# cc3200-shield-v2_0.net
KiCad netlist of a schematic drawn in EAGLE
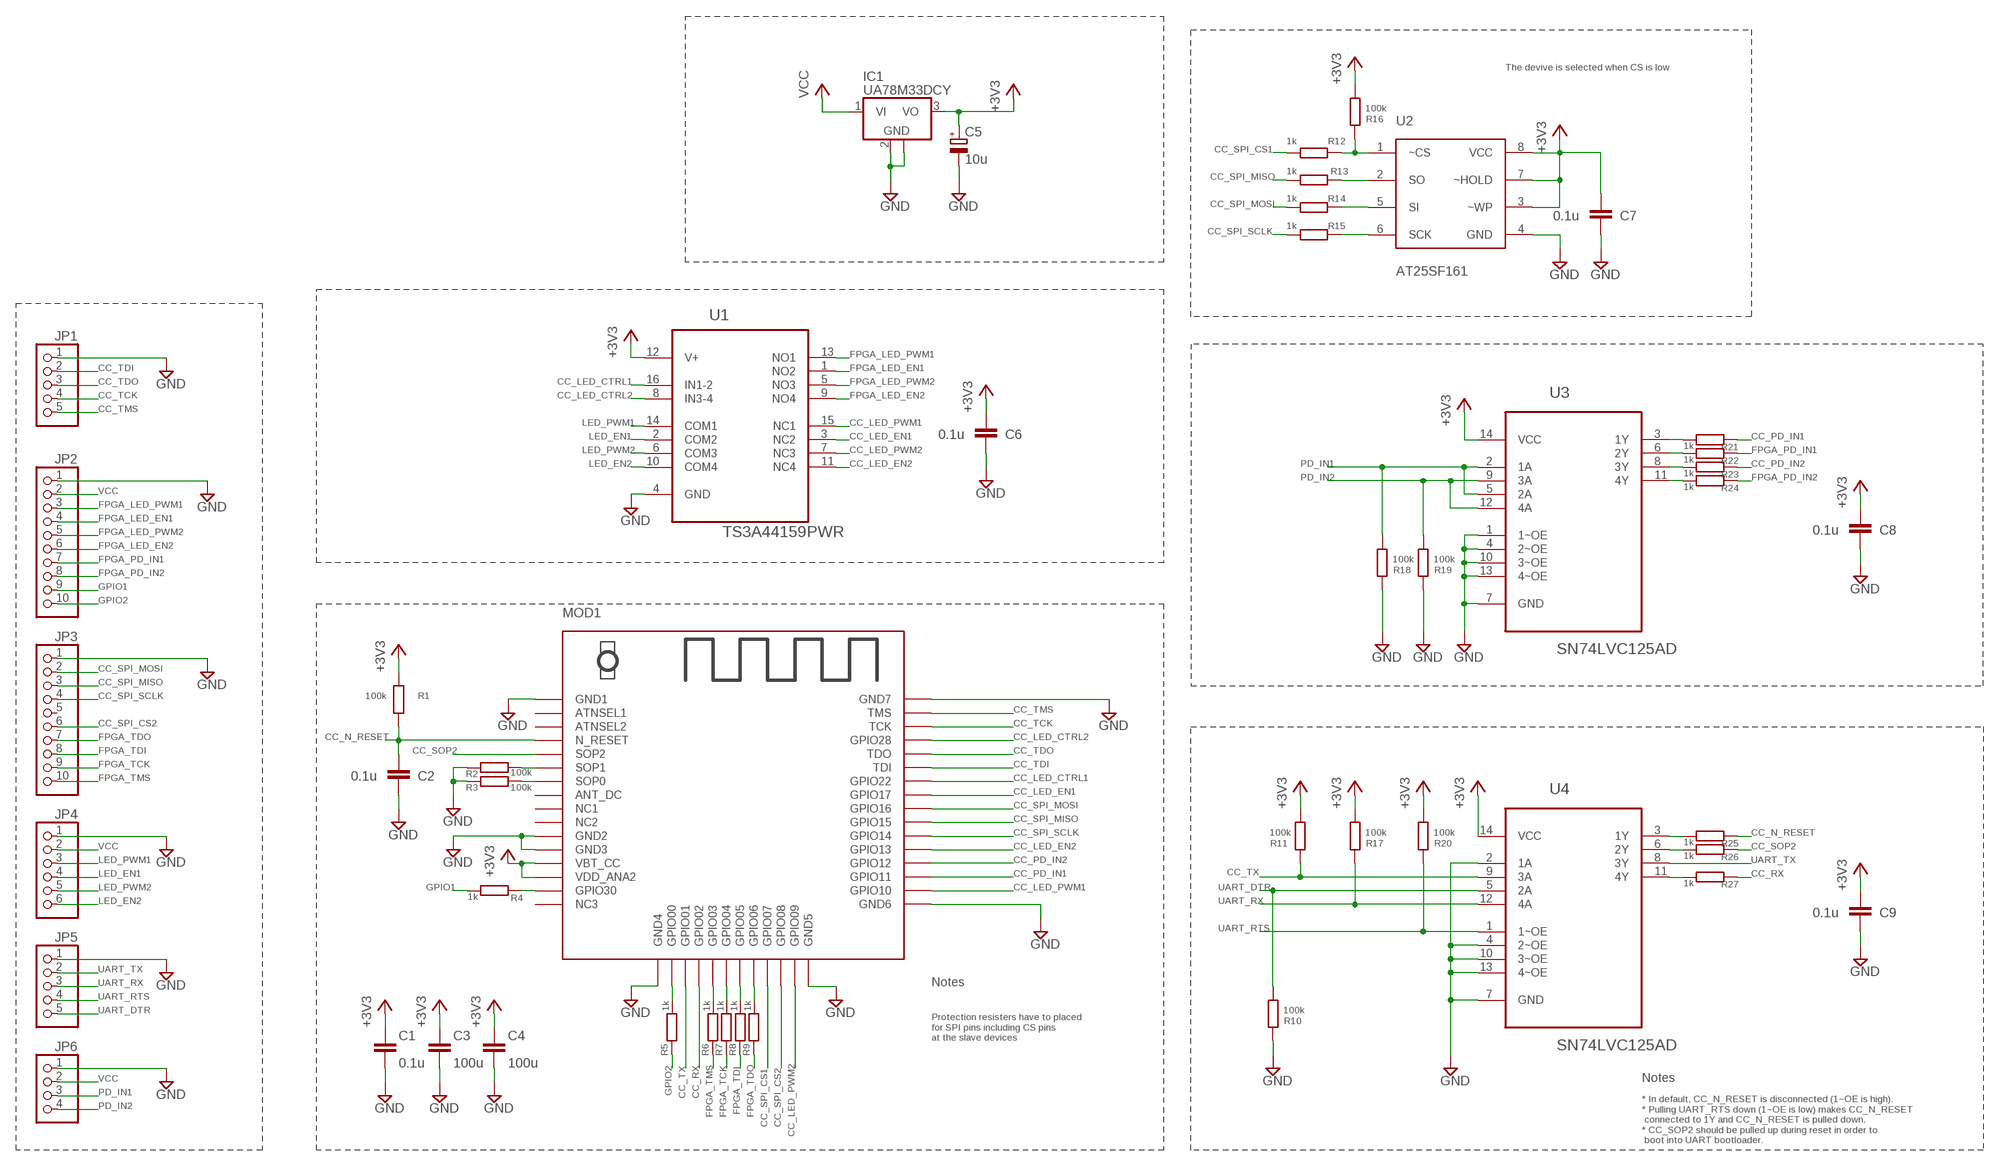
[diagram p0: schematic, sheet 1]

(export (version "E")
  (design (tool "Eeschema 10.0.6"))
  (components
    (comp (ref "C1")
      (value "0.1u")
      (footprint "eagle-import:C0805")
      (libsource (lib "eagle-import") (part "C-EUC0805"))
    )
    (comp (ref "C2")
      (value "0.1u")
      (footprint "eagle-import:C0805")
      (libsource (lib "eagle-import") (part "C-EUC0805"))
    )
    (comp (ref "C3")
      (value "100u")
      (footprint "eagle-import:C1210")
      (libsource (lib "eagle-import") (part "C-EUC1210"))
    )
    (comp (ref "C4")
      (value "100u")
      (footprint "eagle-import:C1210")
      (libsource (lib "eagle-import") (part "C-EUC1210"))
    )
    (comp (ref "C5")
      (value "10u")
      (footprint "eagle-import:153CLV-0405")
      (libsource (lib "eagle-import") (part "CPOL-EU153CLV-0405"))
    )
    (comp (ref "C6")
      (value "0.1u")
      (footprint "eagle-import:C0805")
      (libsource (lib "eagle-import") (part "C-EUC0805"))
    )
    (comp (ref "C7")
      (value "0.1u")
      (footprint "eagle-import:C0805")
      (libsource (lib "eagle-import") (part "C-EUC0805"))
    )
    (comp (ref "C8")
      (value "0.1u")
      (footprint "eagle-import:C0805")
      (libsource (lib "eagle-import") (part "C-EUC0805"))
    )
    (comp (ref "C9")
      (value "0.1u")
      (footprint "eagle-import:C0805")
      (libsource (lib "eagle-import") (part "C-EUC0805"))
    )
    (comp (ref "IC1")
      (value "UA78M33DCY")
      (footprint "eagle-import:SOT223")
      (libsource (lib "eagle-import") (part "UA78MDCY33"))
    )
    (comp (ref "JP1")
      (value "PINHD-1X51X05-1.27MM")
      (footprint "eagle-import:1X05-1.27MM")
      (libsource (lib "eagle-import") (part "PINHD-1X51X05-1.27MM"))
    )
    (comp (ref "JP2")
      (value "PINHD-1X10")
      (footprint "eagle-import:1X10")
      (libsource (lib "eagle-import") (part "PINHD-1X10"))
    )
    (comp (ref "JP3")
      (value "PINHD-1X10")
      (footprint "eagle-import:1X10")
      (libsource (lib "eagle-import") (part "PINHD-1X10"))
    )
    (comp (ref "JP4")
      (value "PINHD-1X6")
      (footprint "eagle-import:1X06")
      (libsource (lib "eagle-import") (part "PINHD-1X6"))
    )
    (comp (ref "JP5")
      (value "PINHD-1X51X05-1.27MM")
      (footprint "eagle-import:1X05-1.27MM")
      (libsource (lib "eagle-import") (part "PINHD-1X51X05-1.27MM"))
    )
    (comp (ref "JP6")
      (value "PINHD-1X41.27MM")
      (footprint "eagle-import:1X04-1.27MM")
      (libsource (lib "eagle-import") (part "PINHD-1X41.27MM"))
    )
    (comp (ref "MOD1")
      (value "USR-C322")
      (footprint "eagle-import:USR-C322")
      (libsource (lib "eagle-import") (part "USR-C322"))
    )
    (comp (ref "R1")
      (value "100k")
      (footprint "eagle-import:R0805")
      (libsource (lib "eagle-import") (part "R-EU_R0805"))
    )
    (comp (ref "R2")
      (value "100k")
      (footprint "eagle-import:R0805")
      (libsource (lib "eagle-import") (part "R-EU_R0805"))
    )
    (comp (ref "R3")
      (value "100k")
      (footprint "eagle-import:R0805")
      (libsource (lib "eagle-import") (part "R-EU_R0805"))
    )
    (comp (ref "R4")
      (value "1k")
      (footprint "eagle-import:R0805")
      (libsource (lib "eagle-import") (part "R-EU_R0805"))
    )
    (comp (ref "R5")
      (value "1k")
      (footprint "eagle-import:R0805")
      (libsource (lib "eagle-import") (part "R-EU_R0805"))
    )
    (comp (ref "R6")
      (value "1k")
      (footprint "eagle-import:R0805")
      (libsource (lib "eagle-import") (part "R-EU_R0805"))
    )
    (comp (ref "R7")
      (value "1k")
      (footprint "eagle-import:R0805")
      (libsource (lib "eagle-import") (part "R-EU_R0805"))
    )
    (comp (ref "R8")
      (value "1k")
      (footprint "eagle-import:R0805")
      (libsource (lib "eagle-import") (part "R-EU_R0805"))
    )
    (comp (ref "R9")
      (value "1k")
      (footprint "eagle-import:R0805")
      (libsource (lib "eagle-import") (part "R-EU_R0805"))
    )
    (comp (ref "R10")
      (value "100k")
      (footprint "eagle-import:R0805")
      (libsource (lib "eagle-import") (part "R-EU_R0805"))
    )
    (comp (ref "R11")
      (value "100k")
      (footprint "eagle-import:R0805")
      (libsource (lib "eagle-import") (part "R-EU_R0805"))
    )
    (comp (ref "R12")
      (value "1k")
      (footprint "eagle-import:R0805")
      (libsource (lib "eagle-import") (part "R-EU_R0805"))
    )
    (comp (ref "R13")
      (value "1k")
      (footprint "eagle-import:R0805")
      (libsource (lib "eagle-import") (part "R-EU_R0805"))
    )
    (comp (ref "R14")
      (value "1k")
      (footprint "eagle-import:R0805")
      (libsource (lib "eagle-import") (part "R-EU_R0805"))
    )
    (comp (ref "R15")
      (value "1k")
      (footprint "eagle-import:R0805")
      (libsource (lib "eagle-import") (part "R-EU_R0805"))
    )
    (comp (ref "R16")
      (value "100k")
      (footprint "eagle-import:R0805")
      (libsource (lib "eagle-import") (part "R-EU_R0805"))
    )
    (comp (ref "R17")
      (value "100k")
      (footprint "eagle-import:R0805")
      (libsource (lib "eagle-import") (part "R-EU_R0805"))
    )
    (comp (ref "R18")
      (value "100k")
      (footprint "eagle-import:R0805")
      (libsource (lib "eagle-import") (part "R-EU_R0805"))
    )
    (comp (ref "R19")
      (value "100k")
      (footprint "eagle-import:R0805")
      (libsource (lib "eagle-import") (part "R-EU_R0805"))
    )
    (comp (ref "R20")
      (value "100k")
      (footprint "eagle-import:R0805")
      (libsource (lib "eagle-import") (part "R-EU_R0805"))
    )
    (comp (ref "R21")
      (value "1k")
      (footprint "eagle-import:R0805")
      (libsource (lib "eagle-import") (part "R-EU_R0805"))
    )
    (comp (ref "R22")
      (value "1k")
      (footprint "eagle-import:R0805")
      (libsource (lib "eagle-import") (part "R-EU_R0805"))
    )
    (comp (ref "R23")
      (value "1k")
      (footprint "eagle-import:R0805")
      (libsource (lib "eagle-import") (part "R-EU_R0805"))
    )
    (comp (ref "R24")
      (value "1k")
      (footprint "eagle-import:R0805")
      (libsource (lib "eagle-import") (part "R-EU_R0805"))
    )
    (comp (ref "R25")
      (value "1k")
      (footprint "eagle-import:R0805")
      (libsource (lib "eagle-import") (part "R-EU_R0805"))
    )
    (comp (ref "R26")
      (value "1k")
      (footprint "eagle-import:R0805")
      (libsource (lib "eagle-import") (part "R-EU_R0805"))
    )
    (comp (ref "R27")
      (value "1k")
      (footprint "eagle-import:R0805")
      (libsource (lib "eagle-import") (part "R-EU_R0805"))
    )
    (comp (ref "U1")
      (value "TS3A44159PWR")
      (footprint "eagle-import:SOP65P640X120-16N")
      (libsource (lib "eagle-import") (part "TS3A44159PWR"))
    )
    (comp (ref "U2")
      (value "AT25SF161")
      (footprint "eagle-import:SO08")
      (libsource (lib "eagle-import") (part "AT25SF161"))
    )
    (comp (ref "U3")
      (value "SN74LVC125AD")
      (footprint "eagle-import:SOIC127P600X175-14N")
      (libsource (lib "eagle-import") (part "SN74LVC125AD"))
    )
    (comp (ref "U4")
      (value "SN74LVC125AD")
      (footprint "eagle-import:SOIC127P600X175-14N")
      (libsource (lib "eagle-import") (part "SN74LVC125AD"))
    )
  )
  (nets
    (net (code "1") (name "+3V3") (class "Default")
      (node (ref "C1") (pin "1") (pinfunction "1_1") (pintype "passive"))
      (node (ref "C3") (pin "1") (pinfunction "1_1") (pintype "passive"))
      (node (ref "C4") (pin "1") (pinfunction "1_1") (pintype "passive"))
      (node (ref "C5") (pin "+") (pinfunction "+_+") (pintype "passive"))
      (node (ref "C6") (pin "1") (pinfunction "1_1") (pintype "passive"))
      (node (ref "C7") (pin "1") (pinfunction "1_1") (pintype "passive"))
      (node (ref "C8") (pin "1") (pinfunction "1_1") (pintype "passive"))
      (node (ref "C9") (pin "1") (pinfunction "1_1") (pintype "passive"))
      (node (ref "IC1") (pin "3") (pinfunction "VO_3") (pintype "passive"))
      (node (ref "MOD1") (pin "VBT_CC") (pinfunction "VBT_CC_VBT_CC") (pintype "bidirectional"))
      (node (ref "MOD1") (pin "VDD_ANT") (pinfunction "VDD_ANA2_VDD_ANT") (pintype "bidirectional"))
      (node (ref "R1") (pin "2") (pinfunction "2_2") (pintype "passive"))
      (node (ref "R11") (pin "2") (pinfunction "2_2") (pintype "passive"))
      (node (ref "R16") (pin "2") (pinfunction "2_2") (pintype "passive"))
      (node (ref "R17") (pin "2") (pinfunction "2_2") (pintype "passive"))
      (node (ref "R20") (pin "2") (pinfunction "2_2") (pintype "passive"))
      (node (ref "U1") (pin "12") (pinfunction "V+_12") (pintype "power_in"))
      (node (ref "U2") (pin "3") (pinfunction "~{WP}_3") (pintype "bidirectional"))
      (node (ref "U2") (pin "7") (pinfunction "~{HOLD}_7") (pintype "bidirectional"))
      (node (ref "U2") (pin "8") (pinfunction "VCC_8") (pintype "bidirectional"))
      (node (ref "U3") (pin "14") (pinfunction "VCC_14") (pintype "power_in"))
      (node (ref "U4") (pin "14") (pinfunction "VCC_14") (pintype "power_in"))
    )
    (net (code "2") (name "/CC_LED_CTRL1") (class "Default")
      (node (ref "MOD1") (pin "GPIO22") (pinfunction "GPIO22_GPIO22") (pintype "bidirectional"))
      (node (ref "U1") (pin "16") (pinfunction "IN1-2_16") (pintype "input"))
    )
    (net (code "3") (name "/CC_LED_CTRL2") (class "Default")
      (node (ref "MOD1") (pin "GPIO28") (pinfunction "GPIO28_GPIO28") (pintype "bidirectional"))
      (node (ref "U1") (pin "8") (pinfunction "IN3-4_8") (pintype "input"))
    )
    (net (code "4") (name "/CC_LED_EN1") (class "Default")
      (node (ref "MOD1") (pin "GPIO17") (pinfunction "GPIO17_GPIO17") (pintype "bidirectional"))
      (node (ref "U1") (pin "3") (pinfunction "NC2_3") (pintype "passive"))
    )
    (net (code "5") (name "/CC_LED_EN2") (class "Default")
      (node (ref "MOD1") (pin "GPIO13") (pinfunction "GPIO13_GPIO13") (pintype "bidirectional"))
      (node (ref "U1") (pin "11") (pinfunction "NC4_11") (pintype "passive"))
    )
    (net (code "6") (name "/CC_LED_PWM1") (class "Default")
      (node (ref "MOD1") (pin "GPIO10") (pinfunction "GPIO10_GPIO10") (pintype "bidirectional"))
      (node (ref "U1") (pin "15") (pinfunction "NC1_15") (pintype "passive"))
    )
    (net (code "7") (name "/CC_LED_PWM2") (class "Default")
      (node (ref "MOD1") (pin "GPIO09") (pinfunction "GPIO09_GPIO09") (pintype "bidirectional"))
      (node (ref "U1") (pin "7") (pinfunction "NC3_7") (pintype "passive"))
    )
    (net (code "8") (name "/CC_N_RESET") (class "Default")
      (node (ref "C2") (pin "1") (pinfunction "1_1") (pintype "passive"))
      (node (ref "MOD1") (pin "N_RESET") (pinfunction "N_RESET_N_RESET") (pintype "bidirectional"))
      (node (ref "R1") (pin "1") (pinfunction "1_1") (pintype "passive"))
      (node (ref "R25") (pin "1") (pinfunction "1_1") (pintype "passive"))
    )
    (net (code "9") (name "/CC_PD_IN1") (class "Default")
      (node (ref "MOD1") (pin "GPIO11") (pinfunction "GPIO11_GPIO11") (pintype "bidirectional"))
      (node (ref "R21") (pin "1") (pinfunction "1_1") (pintype "passive"))
    )
    (net (code "10") (name "/CC_PD_IN2") (class "Default")
      (node (ref "MOD1") (pin "GPIO12") (pinfunction "GPIO12_GPIO12") (pintype "bidirectional"))
      (node (ref "R23") (pin "1") (pinfunction "1_1") (pintype "passive"))
    )
    (net (code "11") (name "/CC_RX") (class "Default")
      (node (ref "MOD1") (pin "GPIO02") (pinfunction "GPIO02_GPIO02") (pintype "bidirectional"))
      (node (ref "R27") (pin "1") (pinfunction "1_1") (pintype "passive"))
    )
    (net (code "12") (name "/CC_SOP2") (class "Default")
      (node (ref "MOD1") (pin "SOP2") (pinfunction "SOP2_SOP2") (pintype "bidirectional"))
      (node (ref "R26") (pin "1") (pinfunction "1_1") (pintype "passive"))
    )
    (net (code "13") (name "/CC_SPI_CS1") (class "Default")
      (node (ref "MOD1") (pin "GPIO07") (pinfunction "GPIO07_GPIO07") (pintype "bidirectional"))
      (node (ref "R12") (pin "2") (pinfunction "2_2") (pintype "passive"))
    )
    (net (code "14") (name "/CC_SPI_CS2") (class "Default")
      (node (ref "JP3") (pin "6") (pinfunction "6_6") (pintype "passive"))
      (node (ref "MOD1") (pin "GPIO08") (pinfunction "GPIO08_GPIO08") (pintype "bidirectional"))
    )
    (net (code "15") (name "/CC_SPI_MISO") (class "Default")
      (node (ref "JP3") (pin "3") (pinfunction "3_3") (pintype "passive"))
      (node (ref "MOD1") (pin "SPI_MISO/GPIO15") (pinfunction "GPIO15_SPI_MISO/GPIO15") (pintype "bidirectional"))
      (node (ref "R13") (pin "2") (pinfunction "2_2") (pintype "passive"))
    )
    (net (code "16") (name "/CC_SPI_MOSI") (class "Default")
      (node (ref "JP3") (pin "2") (pinfunction "2_2") (pintype "passive"))
      (node (ref "MOD1") (pin "GPIO16") (pinfunction "GPIO16_GPIO16") (pintype "bidirectional"))
      (node (ref "R14") (pin "2") (pinfunction "2_2") (pintype "passive"))
    )
    (net (code "17") (name "/CC_SPI_SCLK") (class "Default")
      (node (ref "JP3") (pin "4") (pinfunction "4_4") (pintype "passive"))
      (node (ref "MOD1") (pin "GPIO14") (pinfunction "GPIO14_GPIO14") (pintype "bidirectional"))
      (node (ref "R15") (pin "2") (pinfunction "2_2") (pintype "passive"))
    )
    (net (code "18") (name "/CC_TCK") (class "Default")
      (node (ref "JP1") (pin "4") (pinfunction "4_4") (pintype "passive"))
      (node (ref "MOD1") (pin "TCK") (pinfunction "TCK_TCK") (pintype "bidirectional"))
    )
    (net (code "19") (name "/CC_TDI") (class "Default")
      (node (ref "JP1") (pin "2") (pinfunction "2_2") (pintype "passive"))
      (node (ref "MOD1") (pin "TDI") (pinfunction "TDI_TDI") (pintype "bidirectional"))
    )
    (net (code "20") (name "/CC_TDO") (class "Default")
      (node (ref "JP1") (pin "3") (pinfunction "3_3") (pintype "passive"))
      (node (ref "MOD1") (pin "TDO") (pinfunction "TDO_TDO") (pintype "bidirectional"))
    )
    (net (code "21") (name "/CC_TMS") (class "Default")
      (node (ref "JP1") (pin "5") (pinfunction "5_5") (pintype "passive"))
      (node (ref "MOD1") (pin "TMS") (pinfunction "TMS_TMS") (pintype "bidirectional"))
    )
    (net (code "22") (name "/CC_TX") (class "Default")
      (node (ref "MOD1") (pin "GPIO01") (pinfunction "GPIO01_GPIO01") (pintype "bidirectional"))
      (node (ref "R11") (pin "1") (pinfunction "1_1") (pintype "passive"))
      (node (ref "U4") (pin "9") (pinfunction "3A_9") (pintype "input"))
    )
    (net (code "23") (name "/FPGA_LED_EN1") (class "Default")
      (node (ref "JP2") (pin "4") (pinfunction "4_4") (pintype "passive"))
      (node (ref "U1") (pin "1") (pinfunction "NO2_1") (pintype "passive"))
    )
    (net (code "24") (name "/FPGA_LED_EN2") (class "Default")
      (node (ref "JP2") (pin "6") (pinfunction "6_6") (pintype "passive"))
      (node (ref "U1") (pin "9") (pinfunction "NO4_9") (pintype "passive"))
    )
    (net (code "25") (name "/FPGA_LED_PWM1") (class "Default")
      (node (ref "JP2") (pin "3") (pinfunction "3_3") (pintype "passive"))
      (node (ref "U1") (pin "13") (pinfunction "NO1_13") (pintype "passive"))
    )
    (net (code "26") (name "/FPGA_LED_PWM2") (class "Default")
      (node (ref "JP2") (pin "5") (pinfunction "5_5") (pintype "passive"))
      (node (ref "U1") (pin "5") (pinfunction "NO3_5") (pintype "passive"))
    )
    (net (code "27") (name "/FPGA_PD_IN1") (class "Default")
      (node (ref "JP2") (pin "7") (pinfunction "7_7") (pintype "passive"))
      (node (ref "R22") (pin "1") (pinfunction "1_1") (pintype "passive"))
    )
    (net (code "28") (name "/FPGA_PD_IN2") (class "Default")
      (node (ref "JP2") (pin "8") (pinfunction "8_8") (pintype "passive"))
      (node (ref "R24") (pin "1") (pinfunction "1_1") (pintype "passive"))
    )
    (net (code "29") (name "/FPGA_TCK") (class "Default")
      (node (ref "JP3") (pin "9") (pinfunction "9_9") (pintype "passive"))
      (node (ref "R7") (pin "1") (pinfunction "1_1") (pintype "passive"))
    )
    (net (code "30") (name "/FPGA_TDI") (class "Default")
      (node (ref "JP3") (pin "8") (pinfunction "8_8") (pintype "passive"))
      (node (ref "R8") (pin "1") (pinfunction "1_1") (pintype "passive"))
    )
    (net (code "31") (name "/FPGA_TDO") (class "Default")
      (node (ref "JP3") (pin "7") (pinfunction "7_7") (pintype "passive"))
      (node (ref "R9") (pin "1") (pinfunction "1_1") (pintype "passive"))
    )
    (net (code "32") (name "/FPGA_TMS") (class "Default")
      (node (ref "JP3") (pin "10") (pinfunction "10_10") (pintype "passive"))
      (node (ref "R6") (pin "1") (pinfunction "1_1") (pintype "passive"))
    )
    (net (code "33") (name "/GPIO1") (class "Default")
      (node (ref "JP2") (pin "9") (pinfunction "9_9") (pintype "passive"))
      (node (ref "R4") (pin "2") (pinfunction "2_2") (pintype "passive"))
    )
    (net (code "34") (name "/GPIO2") (class "Default")
      (node (ref "JP2") (pin "10") (pinfunction "10_10") (pintype "passive"))
      (node (ref "R5") (pin "1") (pinfunction "1_1") (pintype "passive"))
    )
    (net (code "35") (name "/LED_EN1") (class "Default")
      (node (ref "JP4") (pin "4") (pinfunction "4_4") (pintype "passive"))
      (node (ref "U1") (pin "2") (pinfunction "COM2_2") (pintype "passive"))
    )
    (net (code "36") (name "/LED_EN2") (class "Default")
      (node (ref "JP4") (pin "6") (pinfunction "6_6") (pintype "passive"))
      (node (ref "U1") (pin "10") (pinfunction "COM4_10") (pintype "passive"))
    )
    (net (code "37") (name "/LED_PWM1") (class "Default")
      (node (ref "JP4") (pin "3") (pinfunction "3_3") (pintype "passive"))
      (node (ref "U1") (pin "14") (pinfunction "COM1_14") (pintype "passive"))
    )
    (net (code "38") (name "/LED_PWM2") (class "Default")
      (node (ref "JP4") (pin "5") (pinfunction "5_5") (pintype "passive"))
      (node (ref "U1") (pin "6") (pinfunction "COM3_6") (pintype "passive"))
    )
    (net (code "39") (name "/PD_IN1") (class "Default")
      (node (ref "JP6") (pin "3") (pinfunction "3_3") (pintype "passive"))
      (node (ref "R18") (pin "2") (pinfunction "2_2") (pintype "passive"))
      (node (ref "U3") (pin "2") (pinfunction "1A_2") (pintype "input"))
      (node (ref "U3") (pin "5") (pinfunction "2A_5") (pintype "input"))
    )
    (net (code "40") (name "/PD_IN2") (class "Default")
      (node (ref "JP6") (pin "4") (pinfunction "4_4") (pintype "passive"))
      (node (ref "R19") (pin "2") (pinfunction "2_2") (pintype "passive"))
      (node (ref "U3") (pin "12") (pinfunction "4A_12") (pintype "input"))
      (node (ref "U3") (pin "9") (pinfunction "3A_9") (pintype "input"))
    )
    (net (code "41") (name "/UART_DTR") (class "Default")
      (node (ref "JP5") (pin "5") (pinfunction "5_5") (pintype "passive"))
      (node (ref "R10") (pin "2") (pinfunction "2_2") (pintype "passive"))
      (node (ref "U4") (pin "5") (pinfunction "2A_5") (pintype "input"))
    )
    (net (code "42") (name "/UART_RTS") (class "Default")
      (node (ref "JP5") (pin "4") (pinfunction "4_4") (pintype "passive"))
      (node (ref "R20") (pin "1") (pinfunction "1_1") (pintype "passive"))
      (node (ref "U4") (pin "1") (pinfunction "1~{OE}_1") (pintype "input"))
    )
    (net (code "43") (name "/UART_RX") (class "Default")
      (node (ref "JP5") (pin "3") (pinfunction "3_3") (pintype "passive"))
      (node (ref "R17") (pin "1") (pinfunction "1_1") (pintype "passive"))
      (node (ref "U4") (pin "12") (pinfunction "4A_12") (pintype "input"))
    )
    (net (code "44") (name "/UART_TX") (class "Default")
      (node (ref "JP5") (pin "2") (pinfunction "2_2") (pintype "passive"))
      (node (ref "U4") (pin "8") (pinfunction "3Y_8") (pintype "output"))
    )
    (net (code "45") (name "GND") (class "Default")
      (node (ref "C1") (pin "2") (pinfunction "2_2") (pintype "passive"))
      (node (ref "C2") (pin "2") (pinfunction "2_2") (pintype "passive"))
      (node (ref "C3") (pin "2") (pinfunction "2_2") (pintype "passive"))
      (node (ref "C4") (pin "2") (pinfunction "2_2") (pintype "passive"))
      (node (ref "C5") (pin "-") (pinfunction "-_-") (pintype "passive"))
      (node (ref "C6") (pin "2") (pinfunction "2_2") (pintype "passive"))
      (node (ref "C7") (pin "2") (pinfunction "2_2") (pintype "passive"))
      (node (ref "C8") (pin "2") (pinfunction "2_2") (pintype "passive"))
      (node (ref "C9") (pin "2") (pinfunction "2_2") (pintype "passive"))
      (node (ref "IC1") (pin "2") (pinfunction "GND_2") (pintype "passive"))
      (node (ref "IC1") (pin "4") (pinfunction "GND_4") (pintype "passive"))
      (node (ref "JP1") (pin "1") (pinfunction "1_1") (pintype "passive"))
      (node (ref "JP2") (pin "1") (pinfunction "1_1") (pintype "passive"))
      (node (ref "JP3") (pin "1") (pinfunction "1_1") (pintype "passive"))
      (node (ref "JP4") (pin "1") (pinfunction "1_1") (pintype "passive"))
      (node (ref "JP5") (pin "1") (pinfunction "1_1") (pintype "passive"))
      (node (ref "JP6") (pin "1") (pinfunction "1_1") (pintype "passive"))
      (node (ref "MOD1") (pin "GND1") (pinfunction "GND1_GND1") (pintype "bidirectional"))
      (node (ref "MOD1") (pin "GND2") (pinfunction "GND2_GND2") (pintype "bidirectional"))
      (node (ref "MOD1") (pin "GND3") (pinfunction "GND3_GND3") (pintype "bidirectional"))
      (node (ref "MOD1") (pin "GND4") (pinfunction "GND4_GND4") (pintype "bidirectional"))
      (node (ref "MOD1") (pin "GND5") (pinfunction "GND5_GND5") (pintype "bidirectional"))
      (node (ref "MOD1") (pin "GND6") (pinfunction "GND6_GND6") (pintype "bidirectional"))
      (node (ref "MOD1") (pin "GND7") (pinfunction "GND7_GND7") (pintype "bidirectional"))
      (node (ref "R10") (pin "1") (pinfunction "1_1") (pintype "passive"))
      (node (ref "R18") (pin "1") (pinfunction "1_1") (pintype "passive"))
      (node (ref "R19") (pin "1") (pinfunction "1_1") (pintype "passive"))
      (node (ref "R2") (pin "1") (pinfunction "1_1") (pintype "passive"))
      (node (ref "R3") (pin "1") (pinfunction "1_1") (pintype "passive"))
      (node (ref "U1") (pin "4") (pinfunction "GND_4") (pintype "passive"))
      (node (ref "U2") (pin "4") (pinfunction "GND_4") (pintype "bidirectional"))
      (node (ref "U3") (pin "1") (pinfunction "1~{OE}_1") (pintype "input"))
      (node (ref "U3") (pin "10") (pinfunction "3~{OE}_10") (pintype "input"))
      (node (ref "U3") (pin "13") (pinfunction "4~{OE}_13") (pintype "input"))
      (node (ref "U3") (pin "4") (pinfunction "2~{OE}_4") (pintype "input"))
      (node (ref "U3") (pin "7") (pinfunction "GND_7") (pintype "passive"))
      (node (ref "U4") (pin "10") (pinfunction "3~{OE}_10") (pintype "input"))
      (node (ref "U4") (pin "13") (pinfunction "4~{OE}_13") (pintype "input"))
      (node (ref "U4") (pin "2") (pinfunction "1A_2") (pintype "input"))
      (node (ref "U4") (pin "4") (pinfunction "2~{OE}_4") (pintype "input"))
      (node (ref "U4") (pin "7") (pinfunction "GND_7") (pintype "passive"))
    )
    (net (code "46") (name "Net-(MOD1-PadGPIO00)") (class "Default")
      (node (ref "MOD1") (pin "GPIO00") (pinfunction "GPIO00_GPIO00") (pintype "bidirectional"))
      (node (ref "R5") (pin "2") (pinfunction "2_2") (pintype "passive"))
    )
    (net (code "47") (name "Net-(MOD1-PadGPIO03)") (class "Default")
      (node (ref "MOD1") (pin "GPIO03") (pinfunction "GPIO03_GPIO03") (pintype "bidirectional"))
      (node (ref "R6") (pin "2") (pinfunction "2_2") (pintype "passive"))
    )
    (net (code "48") (name "Net-(MOD1-PadGPIO04)") (class "Default")
      (node (ref "MOD1") (pin "GPIO04") (pinfunction "GPIO04_GPIO04") (pintype "bidirectional"))
      (node (ref "R7") (pin "2") (pinfunction "2_2") (pintype "passive"))
    )
    (net (code "49") (name "Net-(MOD1-PadGPIO05)") (class "Default")
      (node (ref "MOD1") (pin "GPIO05") (pinfunction "GPIO05_GPIO05") (pintype "bidirectional"))
      (node (ref "R8") (pin "2") (pinfunction "2_2") (pintype "passive"))
    )
    (net (code "50") (name "Net-(MOD1-PadGPIO06)") (class "Default")
      (node (ref "MOD1") (pin "GPIO06") (pinfunction "GPIO06_GPIO06") (pintype "bidirectional"))
      (node (ref "R9") (pin "2") (pinfunction "2_2") (pintype "passive"))
    )
    (net (code "51") (name "Net-(MOD1-PadGPIO30)") (class "Default")
      (node (ref "MOD1") (pin "GPIO30") (pinfunction "GPIO30_GPIO30") (pintype "bidirectional"))
      (node (ref "R4") (pin "1") (pinfunction "1_1") (pintype "passive"))
    )
    (net (code "52") (name "Net-(MOD1-PadSOP0)") (class "Default")
      (node (ref "MOD1") (pin "SOP0") (pinfunction "SOP0_SOP0") (pintype "bidirectional"))
      (node (ref "R3") (pin "2") (pinfunction "2_2") (pintype "passive"))
    )
    (net (code "53") (name "Net-(MOD1-PadSOP1)") (class "Default")
      (node (ref "MOD1") (pin "SOP1") (pinfunction "SOP1_SOP1") (pintype "bidirectional"))
      (node (ref "R2") (pin "2") (pinfunction "2_2") (pintype "passive"))
    )
    (net (code "54") (name "Net-(U2-SCK)") (class "Default")
      (node (ref "R15") (pin "1") (pinfunction "1_1") (pintype "passive"))
      (node (ref "U2") (pin "6") (pinfunction "SCK_6") (pintype "bidirectional"))
    )
    (net (code "55") (name "Net-(U2-SI)") (class "Default")
      (node (ref "R14") (pin "1") (pinfunction "1_1") (pintype "passive"))
      (node (ref "U2") (pin "5") (pinfunction "SI_5") (pintype "bidirectional"))
    )
    (net (code "56") (name "Net-(U2-SO)") (class "Default")
      (node (ref "R13") (pin "1") (pinfunction "1_1") (pintype "passive"))
      (node (ref "U2") (pin "2") (pinfunction "SO_2") (pintype "bidirectional"))
    )
    (net (code "57") (name "Net-(U2-~{CS})") (class "Default")
      (node (ref "R12") (pin "1") (pinfunction "1_1") (pintype "passive"))
      (node (ref "R16") (pin "1") (pinfunction "1_1") (pintype "passive"))
      (node (ref "U2") (pin "1") (pinfunction "~{CS}_1") (pintype "bidirectional"))
    )
    (net (code "58") (name "Net-(U3-1Y)") (class "Default")
      (node (ref "R21") (pin "2") (pinfunction "2_2") (pintype "passive"))
      (node (ref "U3") (pin "3") (pinfunction "1Y_3") (pintype "output"))
    )
    (net (code "59") (name "Net-(U3-2Y)") (class "Default")
      (node (ref "R22") (pin "2") (pinfunction "2_2") (pintype "passive"))
      (node (ref "U3") (pin "6") (pinfunction "2Y_6") (pintype "output"))
    )
    (net (code "60") (name "Net-(U3-3Y)") (class "Default")
      (node (ref "R23") (pin "2") (pinfunction "2_2") (pintype "passive"))
      (node (ref "U3") (pin "8") (pinfunction "3Y_8") (pintype "output"))
    )
    (net (code "61") (name "Net-(U3-4Y)") (class "Default")
      (node (ref "R24") (pin "2") (pinfunction "2_2") (pintype "passive"))
      (node (ref "U3") (pin "11") (pinfunction "4Y_11") (pintype "output"))
    )
    (net (code "62") (name "Net-(U4-1Y)") (class "Default")
      (node (ref "R25") (pin "2") (pinfunction "2_2") (pintype "passive"))
      (node (ref "U4") (pin "3") (pinfunction "1Y_3") (pintype "output"))
    )
    (net (code "63") (name "Net-(U4-2Y)") (class "Default")
      (node (ref "R26") (pin "2") (pinfunction "2_2") (pintype "passive"))
      (node (ref "U4") (pin "6") (pinfunction "2Y_6") (pintype "output"))
    )
    (net (code "64") (name "Net-(U4-4Y)") (class "Default")
      (node (ref "R27") (pin "2") (pinfunction "2_2") (pintype "passive"))
      (node (ref "U4") (pin "11") (pinfunction "4Y_11") (pintype "output"))
    )
    (net (code "65") (name "VCC") (class "Default")
      (node (ref "IC1") (pin "1") (pinfunction "VI_1") (pintype "input"))
      (node (ref "JP2") (pin "2") (pinfunction "2_2") (pintype "passive"))
      (node (ref "JP4") (pin "2") (pinfunction "2_2") (pintype "passive"))
      (node (ref "JP6") (pin "2") (pinfunction "2_2") (pintype "passive"))
    )
    (net (code "66") (name "unconnected-(JP3-Pad5)") (class "Default")
      (node (ref "JP3") (pin "5") (pinfunction "5_5") (pintype "passive"))
    )
    (net (code "67") (name "unconnected-(MOD1-PadANT_DC)") (class "Default")
      (node (ref "MOD1") (pin "ANT_DC") (pinfunction "ANT_DC_ANT_DC") (pintype "bidirectional"))
    )
    (net (code "68") (name "unconnected-(MOD1-PadATNSEL1)") (class "Default")
      (node (ref "MOD1") (pin "ATNSEL1") (pinfunction "ATNSEL1_ATNSEL1") (pintype "bidirectional"))
    )
    (net (code "69") (name "unconnected-(MOD1-PadATNSEL2)") (class "Default")
      (node (ref "MOD1") (pin "ATNSEL2") (pinfunction "ATNSEL2_ATNSEL2") (pintype "bidirectional"))
    )
    (net (code "70") (name "unconnected-(MOD1-PadNC1)") (class "Default")
      (node (ref "MOD1") (pin "NC1") (pinfunction "NC1_NC1") (pintype "bidirectional"))
    )
    (net (code "71") (name "unconnected-(MOD1-PadNC2)") (class "Default")
      (node (ref "MOD1") (pin "NC2") (pinfunction "NC2_NC2") (pintype "bidirectional"))
    )
    (net (code "72") (name "unconnected-(MOD1-PadNC3)") (class "Default")
      (node (ref "MOD1") (pin "NC3") (pinfunction "NC3_NC3") (pintype "bidirectional"))
    )
  )
)
